# ESP32S3.net
KiCad netlist of a schematic drawn in Altium Designer
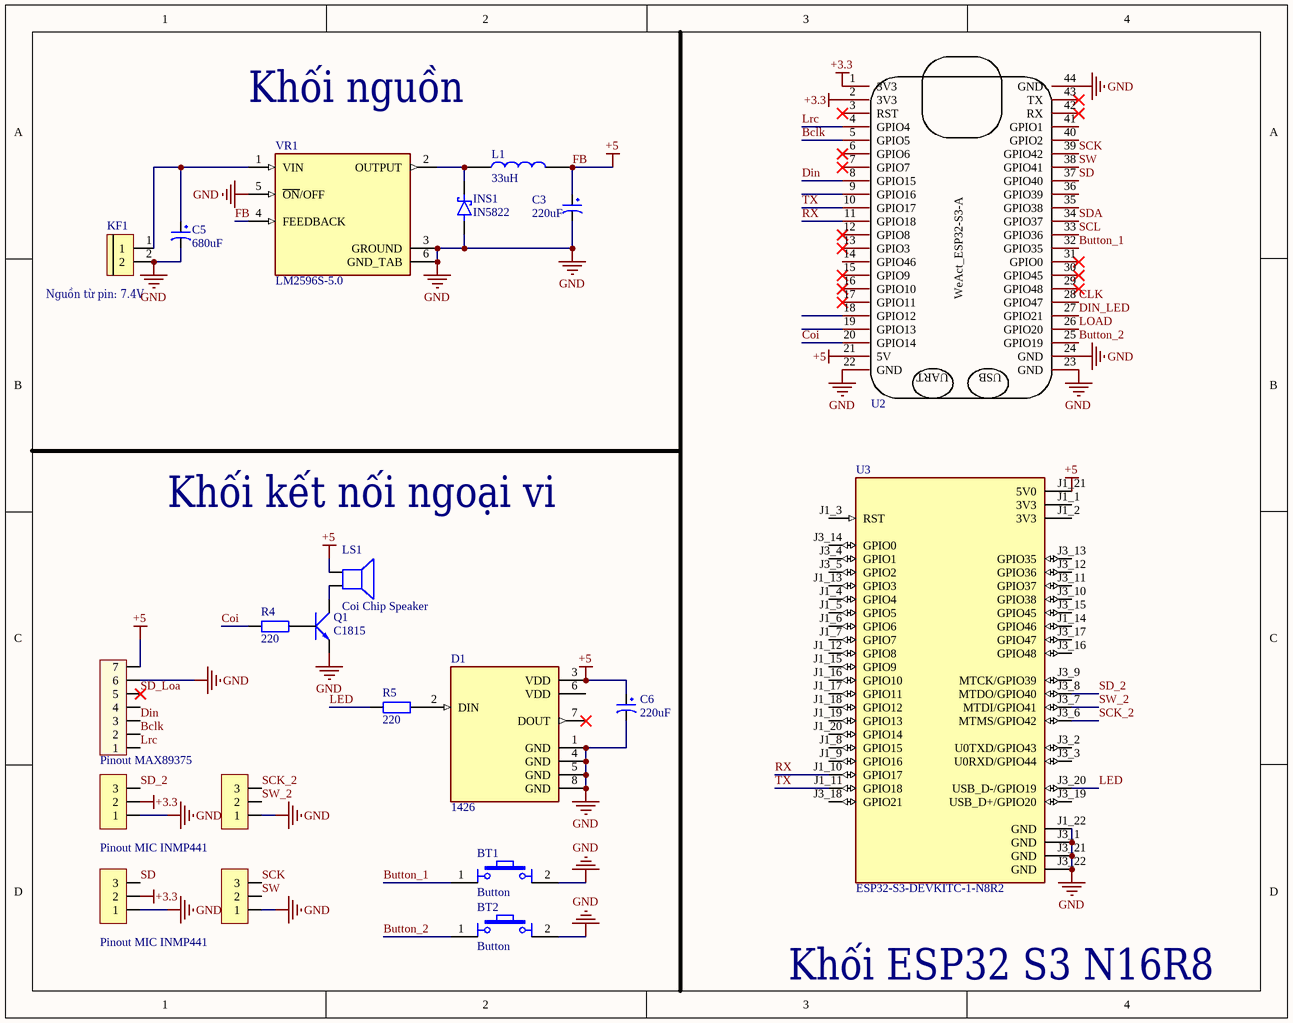
[diagram p0: ESP32S3.SchDoc]

(export (version "E")
  (design (tool "Eeschema 10.0.6"))
  (components
    (comp (ref "BT1")
      (value "Button")
      (footprint "Nut Nhan 4 Chan Cam 6x6")
      (description "Nut Nhan 4 Chan 6x6mm")
      (libsource (lib "Component") (part "Nut Nhan 4 Chan Cam 6x6"))
    )
    (comp (ref "BT2")
      (value "Button")
      (footprint "Nut Nhan 4 Chan Cam 6x6")
      (description "Nut Nhan 4 Chan 6x6mm")
      (libsource (lib "Component") (part "Nut Nhan 4 Chan Cam 6x6"))
    )
    (comp (ref "C3")
      (value "220uF")
      (footprint "Tu Hoa 6.5MM")
      (description "Cắm")
      (libsource (lib "Capacitor") (part "Tu Hoa 22uF 400V 13x20"))
    )
    (comp (ref "C5")
      (value "680uF")
      (footprint "TU HOA 8mm")
      (description "Cắm")
      (libsource (lib "Capacitor") (part "Tu Hoa 22uF 400V 13x20"))
    )
    (comp (ref "C6")
      (value "220uF")
      (footprint "Tu Hoa 6.5MM")
      (description "Cắm")
      (libsource (lib "Capacitor") (part "Tu Hoa 22uF 400V 13x20"))
    )
    (comp (ref "D1")
      (value "1426")
      (footprint "LED_1426")
      (description "NeoPixel Stick - 8 x WS2812 5050 RGB LED with Integrated Drivers ¦ Adafruit Industries 1426")
      (fields (field (name "MF") "Adafruit"))
      (libsource (lib "1426") (part "1426"))
    )
    (comp (ref "H2")
      (value "Pinout MAX89375")
      (footprint "Header 7P DC 2.54")
      (description "Cắm")
      (libsource (lib "Header") (part "Header 7P 2.54 Duc Cong"))
    )
    (comp (ref "INS1")
      (value "IN5822")
      (footprint "DIOM5226X240N")
      (description "Diode Schottky 40V 3A Surface Mount SMA")
      (fields (field (name "MP") "B340A-13-F") (field (name "MF") "Diodes Inc."))
      (libsource (lib "Diode") (part "B340A-13-F"))
    )
    (comp (ref "JP2")
      (value "Pinout MIC INMP441")
      (footprint "JP 1x3 DT")
      (description "Cắm")
      (libsource (lib "Jump") (part "JP 1x3 2.54 Duc Thang"))
    )
    (comp (ref "JP3")
      (value "MIC INMP441")
      (footprint "JP 1x3 DT")
      (description "Cắm")
      (libsource (lib "Jump") (part "JP 1x3 2.54 Duc Thang"))
    )
    (comp (ref "JP4")
      (value "Pinout MIC INMP441")
      (footprint "JP 1x3 DT")
      (description "Cắm")
      (libsource (lib "Jump") (part "JP 1x3 2.54 Duc Thang"))
    )
    (comp (ref "JP5")
      (value "MIC INMP441")
      (footprint "JP 1x3 DT")
      (description "Cắm")
      (libsource (lib "Jump") (part "JP 1x3 2.54 Duc Thang"))
    )
    (comp (ref "KF1")
      (value "Nguồn từ pin: 7.4V")
      (footprint "Con 2 KF301 5.08")
      (description "Cắm")
      (libsource (lib "Connector") (part "CON 2 KF301"))
    )
    (comp (ref "L1")
      (value "33uH")
      (footprint "CUON CAM 100uH3A")
      (description "Dán")
      (libsource (lib "Inductor") (part "CUON CAM 100uH DIP"))
    )
    (comp (ref "LS1")
      (value "Coi Chip Speaker")
      (footprint "Coi Chip Speacker")
      (description "Còi chip")
      (libsource (lib "Component") (part "Coi Chip Speaker"))
    )
    (comp (ref "Q1")
      (value "C1815")
      (footprint "TO92")
      (description "NPN transistor")
      (libsource (lib "TranFet") (part "Trans C1815 DIP"))
    )
    (comp (ref "R4")
      (value "220")
      (footprint "tro smd 1206")
      (description "Dán")
      (libsource (lib "Resistor") (part "Tro 1206 5% 1k"))
    )
    (comp (ref "R5")
      (value "220")
      (footprint "tro smd 1206")
      (description "Dán")
      (libsource (lib "Resistor") (part "Tro 1206 5% 1k"))
    )
    (comp (ref "U2")
      (value "WeAct-ESP32-S3-A")
      (footprint "WeAct-ESP32-S3-A")
      (libsource (lib "WeAct-ESP32-S3-A") (part "WeAct-ESP32-S3-A"))
    )
    (comp (ref "U3")
      (value "ESP32-S3-DEVKITC-1-N8R2")
      (footprint "XCVR_ESP32-S3-DEVKITC-1-N8R2:XCVR_ESP32-S3-DEVKITC-1-N8R2")
      (fields (field (name "MF") "Espressif Systems"))
      (libsource (lib "ESP32-S3-DEVKITC-1-N8R2") (part "ESP32-S3-DEVKITC-1-N8R2"))
    )
    (comp (ref "VR1")
      (value "LM2596S-5.0")
      (footprint "TO170P1524X483-6N")
      (description "SIMPLE SWITCHER&reg; 4.5V to 40V, 3A Low Component Count Step-Down Regulator")
      (fields (field (name "MP") "LM2596S-5.0/NOPB") (field (name "MF") "Texas Instruments"))
      (libsource (lib "LM2596S-5.0") (part "LM2596S-5.0"))
    )
  )
  (nets
    (net (code "1") (name "+3.3") (class "Default")
      (node (ref "JP2") (pin "2") (pinfunction "2_2") (pintype "passive"))
      (node (ref "JP4") (pin "2") (pinfunction "2_2") (pintype "passive"))
      (node (ref "U2") (pin "1") (pinfunction "3V3_1") (pintype "passive"))
      (node (ref "U2") (pin "2") (pinfunction "3V3_2") (pintype "passive"))
    )
    (net (code "2") (name "+5") (class "Default")
      (node (ref "C3") (pin "1") (pinfunction "1_1") (pintype "passive"))
      (node (ref "C6") (pin "1") (pinfunction "1_1") (pintype "passive"))
      (node (ref "D1") (pin "3") (pinfunction "VDD_3") (pintype "power_in"))
      (node (ref "H2") (pin "7") (pinfunction "7_7") (pintype "passive"))
      (node (ref "L1") (pin "2") (pinfunction "2_2") (pintype "passive"))
      (node (ref "LS1") (pin "1") (pinfunction "1_1") (pintype "passive"))
      (node (ref "U2") (pin "21") (pinfunction "5V_21") (pintype "passive"))
      (node (ref "U3") (pin "J1_21") (pinfunction "5V0_J1_21") (pintype "power_in"))
      (node (ref "VR1") (pin "4") (pinfunction "FEEDBACK_4") (pintype "input"))
    )
    (net (code "3") (name "/Bclk") (class "Default")
      (node (ref "H2") (pin "2") (pinfunction "2_2") (pintype "passive"))
      (node (ref "U2") (pin "5") (pinfunction "GPIO5_5") (pintype "passive"))
    )
    (net (code "4") (name "/Button_1") (class "Default")
      (node (ref "BT1") (pin "1") (pintype "passive"))
      (node (ref "U2") (pin "32") (pinfunction "GPIO35_32") (pintype "passive"))
    )
    (net (code "5") (name "/Button_2") (class "Default")
      (node (ref "BT2") (pin "1") (pintype "passive"))
      (node (ref "U2") (pin "25") (pinfunction "GPIO19_25") (pintype "passive"))
    )
    (net (code "6") (name "/CLK") (class "Default")
      (node (ref "U2") (pin "28") (pinfunction "GPIO47_28") (pintype "passive"))
    )
    (net (code "7") (name "/Coi") (class "Default")
      (node (ref "R4") (pin "1") (pinfunction "1_1") (pintype "passive"))
      (node (ref "U2") (pin "20") (pinfunction "GPIO14_20") (pintype "passive"))
    )
    (net (code "8") (name "/DIN_LED") (class "Default")
      (node (ref "U2") (pin "27") (pinfunction "GPIO21_27") (pintype "passive"))
    )
    (net (code "9") (name "/Din") (class "Default")
      (node (ref "H2") (pin "3") (pinfunction "3_3") (pintype "passive"))
      (node (ref "U2") (pin "8") (pinfunction "GPIO15_8") (pintype "passive"))
    )
    (net (code "10") (name "/LED") (class "Default")
      (node (ref "R5") (pin "1") (pinfunction "1_1") (pintype "passive"))
      (node (ref "U3") (pin "J3_20") (pinfunction "USB_D-/GPIO19_J3_20") (pintype "bidirectional"))
    )
    (net (code "11") (name "/LOAD") (class "Default")
      (node (ref "U2") (pin "26") (pinfunction "GPIO20_26") (pintype "passive"))
    )
    (net (code "12") (name "/Lrc") (class "Default")
      (node (ref "H2") (pin "1") (pinfunction "1_1") (pintype "passive"))
      (node (ref "U2") (pin "4") (pinfunction "GPIO4_4") (pintype "passive"))
    )
    (net (code "13") (name "/RX") (class "Default")
      (node (ref "U2") (pin "11") (pinfunction "GPIO18_11") (pintype "passive"))
      (node (ref "U3") (pin "J1_10") (pinfunction "GPIO17_J1_10") (pintype "bidirectional"))
    )
    (net (code "14") (name "/SCK") (class "Default")
      (node (ref "JP5") (pin "3") (pinfunction "3_3") (pintype "passive"))
      (node (ref "U2") (pin "39") (pinfunction "GPIO42_39") (pintype "passive"))
    )
    (net (code "15") (name "/SCK_2") (class "Default")
      (node (ref "JP3") (pin "3") (pinfunction "3_3") (pintype "passive"))
      (node (ref "U3") (pin "J3_6") (pinfunction "MTMS/GPIO42_J3_6") (pintype "bidirectional"))
    )
    (net (code "16") (name "/SCL") (class "Default")
      (node (ref "U2") (pin "33") (pinfunction "GPIO36_33") (pintype "passive"))
    )
    (net (code "17") (name "/SD") (class "Default")
      (node (ref "JP4") (pin "3") (pinfunction "3_3") (pintype "passive"))
      (node (ref "U2") (pin "37") (pinfunction "GPIO40_37") (pintype "passive"))
    )
    (net (code "18") (name "/SDA") (class "Default")
      (node (ref "U2") (pin "34") (pinfunction "GPIO37_34") (pintype "passive"))
    )
    (net (code "19") (name "/SD_2") (class "Default")
      (node (ref "JP2") (pin "3") (pinfunction "3_3") (pintype "passive"))
      (node (ref "U3") (pin "J3_8") (pinfunction "MTDO/GPIO40_J3_8") (pintype "bidirectional"))
    )
    (net (code "20") (name "/SD_Loa") (class "Default")
      (node (ref "H2") (pin "5") (pinfunction "5_5") (pintype "passive+no_connect"))
    )
    (net (code "21") (name "/SW") (class "Default")
      (node (ref "JP5") (pin "2") (pinfunction "2_2") (pintype "passive"))
      (node (ref "U2") (pin "38") (pinfunction "GPIO41_38") (pintype "passive"))
    )
    (net (code "22") (name "/SW_2") (class "Default")
      (node (ref "JP3") (pin "2") (pinfunction "2_2") (pintype "passive"))
      (node (ref "U3") (pin "J3_7") (pinfunction "MTDI/GPIO41_J3_7") (pintype "bidirectional"))
    )
    (net (code "23") (name "/TX") (class "Default")
      (node (ref "U2") (pin "10") (pinfunction "GPIO17_10") (pintype "passive"))
      (node (ref "U3") (pin "J1_11") (pinfunction "GPIO18_J1_11") (pintype "bidirectional"))
    )
    (net (code "24") (name "GND") (class "Default")
      (node (ref "BT1") (pin "2") (pintype "passive"))
      (node (ref "BT2") (pin "2") (pintype "passive"))
      (node (ref "C3") (pin "2") (pinfunction "2_2") (pintype "passive"))
      (node (ref "C5") (pin "2") (pinfunction "2_2") (pintype "passive"))
      (node (ref "C6") (pin "2") (pinfunction "2_2") (pintype "passive"))
      (node (ref "D1") (pin "1") (pinfunction "GND_1") (pintype "power_in"))
      (node (ref "D1") (pin "4") (pinfunction "GND_4") (pintype "power_in"))
      (node (ref "D1") (pin "5") (pinfunction "GND_5") (pintype "power_in"))
      (node (ref "D1") (pin "8") (pinfunction "GND_8") (pintype "power_in"))
      (node (ref "H2") (pin "6") (pinfunction "6_6") (pintype "passive"))
      (node (ref "INS1") (pin "A") (pinfunction "A_A") (pintype "passive"))
      (node (ref "JP2") (pin "1") (pinfunction "1_1") (pintype "passive"))
      (node (ref "JP3") (pin "1") (pinfunction "1_1") (pintype "passive"))
      (node (ref "JP4") (pin "1") (pinfunction "1_1") (pintype "passive"))
      (node (ref "JP5") (pin "1") (pinfunction "1_1") (pintype "passive"))
      (node (ref "KF1") (pin "2") (pinfunction "2_2") (pintype "passive"))
      (node (ref "Q1") (pin "1") (pinfunction "E_1") (pintype "passive"))
      (node (ref "U2") (pin "22") (pinfunction "GND_22") (pintype "passive"))
      (node (ref "U2") (pin "23") (pinfunction "GND_23") (pintype "passive"))
      (node (ref "U2") (pin "24") (pinfunction "GND_24") (pintype "passive"))
      (node (ref "U2") (pin "44") (pinfunction "GND_44") (pintype "passive"))
      (node (ref "U3") (pin "J1_22") (pinfunction "GND_J1_22") (pintype "power_in"))
      (node (ref "U3") (pin "J3_1") (pinfunction "GND_J3_1") (pintype "power_in"))
      (node (ref "U3") (pin "J3_21") (pinfunction "GND_J3_21") (pintype "power_in"))
      (node (ref "U3") (pin "J3_22") (pinfunction "GND_J3_22") (pintype "power_in"))
      (node (ref "VR1") (pin "3") (pinfunction "GROUND_3") (pintype "power_in"))
      (node (ref "VR1") (pin "5") (pinfunction "~{ON}/OFF_5") (pintype "input"))
      (node (ref "VR1") (pin "6") (pinfunction "GND_TAB_6") (pintype "power_in"))
    )
    (net (code "25") (name "Net-(D1-DIN)") (class "Default")
      (node (ref "D1") (pin "2") (pinfunction "DIN_2") (pintype "input"))
      (node (ref "R5") (pin "2") (pinfunction "2_2") (pintype "passive"))
    )
    (net (code "26") (name "Net-(Q1-B)") (class "Default")
      (node (ref "Q1") (pin "3") (pinfunction "B_3") (pintype "passive"))
      (node (ref "R4") (pin "2") (pinfunction "2_2") (pintype "passive"))
    )
    (net (code "27") (name "Net-(Q1-C)") (class "Default")
      (node (ref "LS1") (pin "2") (pinfunction "2_2") (pintype "passive"))
      (node (ref "Q1") (pin "2") (pinfunction "C_2") (pintype "passive"))
    )
    (net (code "28") (name "Net-(VR1-OUTPUT)") (class "Default")
      (node (ref "INS1") (pin "C") (pinfunction "C_C") (pintype "passive"))
      (node (ref "L1") (pin "1") (pinfunction "1_1") (pintype "passive"))
      (node (ref "VR1") (pin "2") (pinfunction "OUTPUT_2") (pintype "output"))
    )
    (net (code "29") (name "Net-(VR1-VIN)") (class "Default")
      (node (ref "C5") (pin "1") (pinfunction "1_1") (pintype "passive"))
      (node (ref "KF1") (pin "1") (pinfunction "1_1") (pintype "passive"))
      (node (ref "VR1") (pin "1") (pinfunction "VIN_1") (pintype "input"))
    )
    (net (code "30") (name "unconnected-(D1-DOUT-Pad7)") (class "Default")
      (node (ref "D1") (pin "7") (pinfunction "DOUT_7") (pintype "output+no_connect"))
    )
    (net (code "31") (name "unconnected-(D1-VDD-Pad6)") (class "Default")
      (node (ref "D1") (pin "6") (pinfunction "VDD_6") (pintype "power_in"))
    )
    (net (code "32") (name "unconnected-(H2-Pad4)") (class "Default")
      (node (ref "H2") (pin "4") (pinfunction "4_4") (pintype "passive"))
    )
    (net (code "33") (name "unconnected-(U2-GPIO0-Pad31)") (class "Default")
      (node (ref "U2") (pin "31") (pinfunction "GPIO0_31") (pintype "passive+no_connect"))
    )
    (net (code "34") (name "unconnected-(U2-GPIO1-Pad41)") (class "Default")
      (node (ref "U2") (pin "41") (pinfunction "GPIO1_41") (pintype "passive"))
    )
    (net (code "35") (name "unconnected-(U2-GPIO2-Pad40)") (class "Default")
      (node (ref "U2") (pin "40") (pinfunction "GPIO2_40") (pintype "passive"))
    )
    (net (code "36") (name "unconnected-(U2-GPIO3-Pad13)") (class "Default")
      (node (ref "U2") (pin "13") (pinfunction "GPIO3_13") (pintype "passive+no_connect"))
    )
    (net (code "37") (name "unconnected-(U2-GPIO6-Pad6)") (class "Default")
      (node (ref "U2") (pin "6") (pinfunction "GPIO6_6") (pintype "passive+no_connect"))
    )
    (net (code "38") (name "unconnected-(U2-GPIO7-Pad7)") (class "Default")
      (node (ref "U2") (pin "7") (pinfunction "GPIO7_7") (pintype "passive+no_connect"))
    )
    (net (code "39") (name "unconnected-(U2-GPIO8-Pad12)") (class "Default")
      (node (ref "U2") (pin "12") (pinfunction "GPIO8_12") (pintype "passive+no_connect"))
    )
    (net (code "40") (name "unconnected-(U2-GPIO9-Pad15)") (class "Default")
      (node (ref "U2") (pin "15") (pinfunction "GPIO9_15") (pintype "passive+no_connect"))
    )
    (net (code "41") (name "unconnected-(U2-GPIO10-Pad16)") (class "Default")
      (node (ref "U2") (pin "16") (pinfunction "GPIO10_16") (pintype "passive+no_connect"))
    )
    (net (code "42") (name "unconnected-(U2-GPIO11-Pad17)") (class "Default")
      (node (ref "U2") (pin "17") (pinfunction "GPIO11_17") (pintype "passive+no_connect"))
    )
    (net (code "43") (name "unconnected-(U2-GPIO12-Pad18)") (class "Default")
      (node (ref "U2") (pin "18") (pinfunction "GPIO12_18") (pintype "passive"))
    )
    (net (code "44") (name "unconnected-(U2-GPIO13-Pad19)") (class "Default")
      (node (ref "U2") (pin "19") (pinfunction "GPIO13_19") (pintype "passive"))
    )
    (net (code "45") (name "unconnected-(U2-GPIO16-Pad9)") (class "Default")
      (node (ref "U2") (pin "9") (pinfunction "GPIO16_9") (pintype "passive"))
    )
    (net (code "46") (name "unconnected-(U2-GPIO38-Pad35)") (class "Default")
      (node (ref "U2") (pin "35") (pinfunction "GPIO38_35") (pintype "passive"))
    )
    (net (code "47") (name "unconnected-(U2-GPIO39-Pad36)") (class "Default")
      (node (ref "U2") (pin "36") (pinfunction "GPIO39_36") (pintype "passive"))
    )
    (net (code "48") (name "unconnected-(U2-GPIO45-Pad30)") (class "Default")
      (node (ref "U2") (pin "30") (pinfunction "GPIO45_30") (pintype "passive+no_connect"))
    )
    (net (code "49") (name "unconnected-(U2-GPIO46-Pad14)") (class "Default")
      (node (ref "U2") (pin "14") (pinfunction "GPIO46_14") (pintype "passive"))
    )
    (net (code "50") (name "unconnected-(U2-GPIO48-Pad29)") (class "Default")
      (node (ref "U2") (pin "29") (pinfunction "GPIO48_29") (pintype "passive+no_connect"))
    )
    (net (code "51") (name "unconnected-(U2-RST-Pad3)") (class "Default")
      (node (ref "U2") (pin "3") (pinfunction "RST_3") (pintype "passive+no_connect"))
    )
    (net (code "52") (name "unconnected-(U2-RX-Pad42)") (class "Default")
      (node (ref "U2") (pin "42") (pinfunction "RX_42") (pintype "passive+no_connect"))
    )
    (net (code "53") (name "unconnected-(U2-TX-Pad43)") (class "Default")
      (node (ref "U2") (pin "43") (pinfunction "TX_43") (pintype "passive+no_connect"))
    )
    (net (code "54") (name "unconnected-(U3-3V3-PadJ1_1)") (class "Default")
      (node (ref "U3") (pin "J1_1") (pinfunction "3V3_J1_1") (pintype "power_in"))
    )
    (net (code "55") (name "unconnected-(U3-3V3-PadJ1_2)") (class "Default")
      (node (ref "U3") (pin "J1_2") (pinfunction "3V3_J1_2") (pintype "power_in"))
    )
    (net (code "56") (name "unconnected-(U3-GPIO0-PadJ3_14)") (class "Default")
      (node (ref "U3") (pin "J3_14") (pinfunction "GPIO0_J3_14") (pintype "bidirectional"))
    )
    (net (code "57") (name "unconnected-(U3-GPIO1-PadJ3_4)") (class "Default")
      (node (ref "U3") (pin "J3_4") (pinfunction "GPIO1_J3_4") (pintype "bidirectional"))
    )
    (net (code "58") (name "unconnected-(U3-GPIO2-PadJ3_5)") (class "Default")
      (node (ref "U3") (pin "J3_5") (pinfunction "GPIO2_J3_5") (pintype "bidirectional"))
    )
    (net (code "59") (name "unconnected-(U3-GPIO3-PadJ1_13)") (class "Default")
      (node (ref "U3") (pin "J1_13") (pinfunction "GPIO3_J1_13") (pintype "bidirectional"))
    )
    (net (code "60") (name "unconnected-(U3-GPIO4-PadJ1_4)") (class "Default")
      (node (ref "U3") (pin "J1_4") (pinfunction "GPIO4_J1_4") (pintype "bidirectional"))
    )
    (net (code "61") (name "unconnected-(U3-GPIO5-PadJ1_5)") (class "Default")
      (node (ref "U3") (pin "J1_5") (pinfunction "GPIO5_J1_5") (pintype "bidirectional"))
    )
    (net (code "62") (name "unconnected-(U3-GPIO6-PadJ1_6)") (class "Default")
      (node (ref "U3") (pin "J1_6") (pinfunction "GPIO6_J1_6") (pintype "bidirectional"))
    )
    (net (code "63") (name "unconnected-(U3-GPIO7-PadJ1_7)") (class "Default")
      (node (ref "U3") (pin "J1_7") (pinfunction "GPIO7_J1_7") (pintype "bidirectional"))
    )
    (net (code "64") (name "unconnected-(U3-GPIO8-PadJ1_12)") (class "Default")
      (node (ref "U3") (pin "J1_12") (pinfunction "GPIO8_J1_12") (pintype "bidirectional"))
    )
    (net (code "65") (name "unconnected-(U3-GPIO9-PadJ1_15)") (class "Default")
      (node (ref "U3") (pin "J1_15") (pinfunction "GPIO9_J1_15") (pintype "bidirectional"))
    )
    (net (code "66") (name "unconnected-(U3-GPIO10-PadJ1_16)") (class "Default")
      (node (ref "U3") (pin "J1_16") (pinfunction "GPIO10_J1_16") (pintype "bidirectional"))
    )
    (net (code "67") (name "unconnected-(U3-GPIO11-PadJ1_17)") (class "Default")
      (node (ref "U3") (pin "J1_17") (pinfunction "GPIO11_J1_17") (pintype "bidirectional"))
    )
    (net (code "68") (name "unconnected-(U3-GPIO12-PadJ1_18)") (class "Default")
      (node (ref "U3") (pin "J1_18") (pinfunction "GPIO12_J1_18") (pintype "bidirectional"))
    )
    (net (code "69") (name "unconnected-(U3-GPIO13-PadJ1_19)") (class "Default")
      (node (ref "U3") (pin "J1_19") (pinfunction "GPIO13_J1_19") (pintype "bidirectional"))
    )
    (net (code "70") (name "unconnected-(U3-GPIO14-PadJ1_20)") (class "Default")
      (node (ref "U3") (pin "J1_20") (pinfunction "GPIO14_J1_20") (pintype "bidirectional"))
    )
    (net (code "71") (name "unconnected-(U3-GPIO15-PadJ1_8)") (class "Default")
      (node (ref "U3") (pin "J1_8") (pinfunction "GPIO15_J1_8") (pintype "bidirectional"))
    )
    (net (code "72") (name "unconnected-(U3-GPIO16-PadJ1_9)") (class "Default")
      (node (ref "U3") (pin "J1_9") (pinfunction "GPIO16_J1_9") (pintype "bidirectional"))
    )
    (net (code "73") (name "unconnected-(U3-GPIO21-PadJ3_18)") (class "Default")
      (node (ref "U3") (pin "J3_18") (pinfunction "GPIO21_J3_18") (pintype "bidirectional"))
    )
    (net (code "74") (name "unconnected-(U3-GPIO35-PadJ3_13)") (class "Default")
      (node (ref "U3") (pin "J3_13") (pinfunction "GPIO35_J3_13") (pintype "bidirectional"))
    )
    (net (code "75") (name "unconnected-(U3-GPIO36-PadJ3_12)") (class "Default")
      (node (ref "U3") (pin "J3_12") (pinfunction "GPIO36_J3_12") (pintype "bidirectional"))
    )
    (net (code "76") (name "unconnected-(U3-GPIO37-PadJ3_11)") (class "Default")
      (node (ref "U3") (pin "J3_11") (pinfunction "GPIO37_J3_11") (pintype "bidirectional"))
    )
    (net (code "77") (name "unconnected-(U3-GPIO38-PadJ3_10)") (class "Default")
      (node (ref "U3") (pin "J3_10") (pinfunction "GPIO38_J3_10") (pintype "bidirectional"))
    )
    (net (code "78") (name "unconnected-(U3-GPIO45-PadJ3_15)") (class "Default")
      (node (ref "U3") (pin "J3_15") (pinfunction "GPIO45_J3_15") (pintype "bidirectional"))
    )
    (net (code "79") (name "unconnected-(U3-GPIO46-PadJ1_14)") (class "Default")
      (node (ref "U3") (pin "J1_14") (pinfunction "GPIO46_J1_14") (pintype "bidirectional"))
    )
    (net (code "80") (name "unconnected-(U3-GPIO47-PadJ3_17)") (class "Default")
      (node (ref "U3") (pin "J3_17") (pinfunction "GPIO47_J3_17") (pintype "bidirectional"))
    )
    (net (code "81") (name "unconnected-(U3-GPIO48-PadJ3_16)") (class "Default")
      (node (ref "U3") (pin "J3_16") (pinfunction "GPIO48_J3_16") (pintype "bidirectional"))
    )
    (net (code "82") (name "unconnected-(U3-MTCK{slash}GPIO39-PadJ3_9)") (class "Default")
      (node (ref "U3") (pin "J3_9") (pinfunction "MTCK/GPIO39_J3_9") (pintype "bidirectional"))
    )
    (net (code "83") (name "unconnected-(U3-RST-PadJ1_3)") (class "Default")
      (node (ref "U3") (pin "J1_3") (pinfunction "RST_J1_3") (pintype "input"))
    )
    (net (code "84") (name "unconnected-(U3-U0RXD{slash}GPIO44-PadJ3_3)") (class "Default")
      (node (ref "U3") (pin "J3_3") (pinfunction "U0RXD/GPIO44_J3_3") (pintype "bidirectional"))
    )
    (net (code "85") (name "unconnected-(U3-U0TXD{slash}GPIO43-PadJ3_2)") (class "Default")
      (node (ref "U3") (pin "J3_2") (pinfunction "U0TXD/GPIO43_J3_2") (pintype "bidirectional"))
    )
    (net (code "86") (name "unconnected-(U3-USB_D+{slash}GPIO20-PadJ3_19)") (class "Default")
      (node (ref "U3") (pin "J3_19") (pinfunction "USB_D+/GPIO20_J3_19") (pintype "bidirectional"))
    )
  )
)
